# Chip_Inputs.net
KiCad netlist of a schematic drawn in Altium Designer
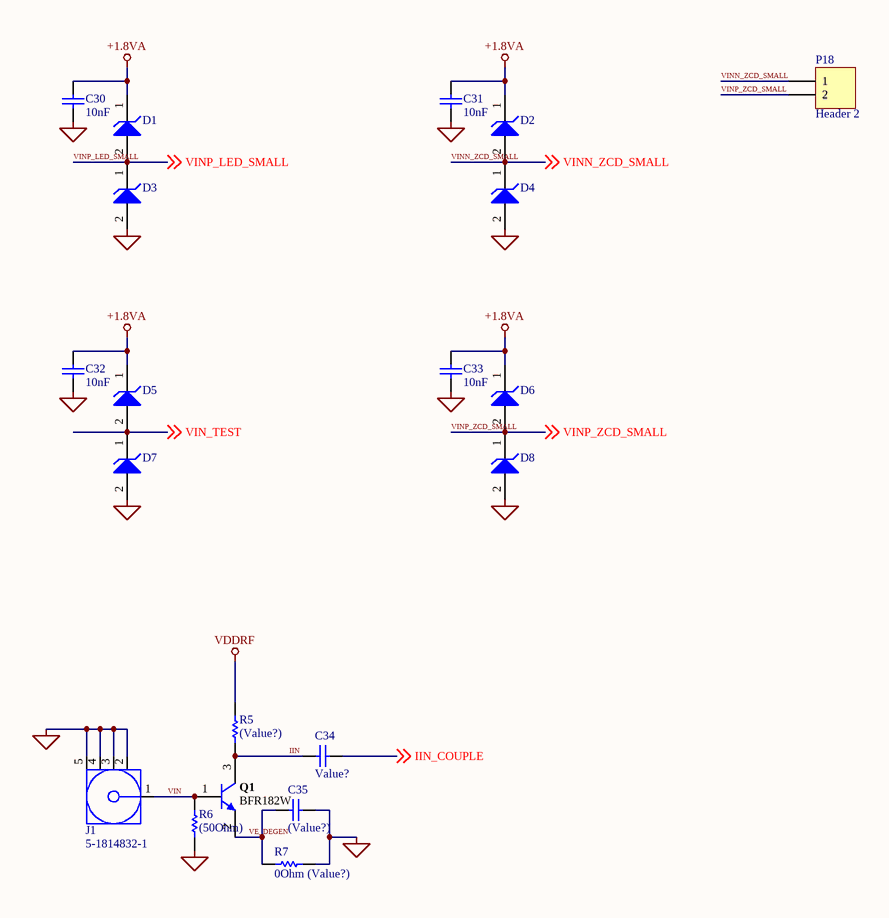
[diagram p0: Chip_Inputs.SchDoc]

(export (version "E")
  (design (tool "Eeschema 10.0.6"))
  (components
    (comp (ref "C30")
      (value "10nF")
      (footprint "CAPC1608X90X35ML10T15")
      (description "0603")
      (fields (field (name "MANUFACTURER") "Murata"))
      (libsource (lib "Altium Content Vault") (part "CAP-NP-2"))
    )
    (comp (ref "C31")
      (value "10nF")
      (footprint "CAPC1608X90X35ML10T15")
      (description "0603")
      (fields (field (name "MANUFACTURER") "Murata"))
      (libsource (lib "Altium Content Vault") (part "CAP-NP-2"))
    )
    (comp (ref "C32")
      (value "10nF")
      (footprint "CAPC1608X90X35ML10T15")
      (description "0603")
      (fields (field (name "MANUFACTURER") "Murata"))
      (libsource (lib "Altium Content Vault") (part "CAP-NP-2"))
    )
    (comp (ref "C33")
      (value "10nF")
      (footprint "CAPC1608X90X35ML10T15")
      (description "0603")
      (fields (field (name "MANUFACTURER") "Murata"))
      (libsource (lib "Altium Content Vault") (part "CAP-NP-2"))
    )
    (comp (ref "C34")
      (value "Value?")
      (footprint "CAPC1608X90X35ML10T15")
      (description "0603")
      (fields (field (name "MANUFACTURER") "Murata"))
      (libsource (lib "Altium Content Vault") (part "CAP-NP-2"))
    )
    (comp (ref "C35")
      (value "(Value?)")
      (footprint "CAPC1608X90X35ML10T15")
      (description "0603")
      (fields (field (name "MANUFACTURER") "Murata"))
      (libsource (lib "Altium Content Vault") (part "CAP-NP-2"))
    )
    (comp (ref "D1")
      (value "~")
      (footprint "ONSC-SOD-123-2-425-04_V")
      (description "Zener Voltage Regulator, 2-Pin SOD-123, Pb-Free, Tape and Reel")
      (fields (field (name "MANUFACTURER") "On Semiconductor") (field (name "PARTNUMBER") "MMSZ4679T1G"))
      (libsource (lib "Altium Content Vault") (part "ONSC-K1A2-2"))
    )
    (comp (ref "D2")
      (value "~")
      (footprint "ONSC-SOD-123-2-425-04_V")
      (description "Zener Voltage Regulator, 2-Pin SOD-123, Pb-Free, Tape and Reel")
      (fields (field (name "MANUFACTURER") "On Semiconductor") (field (name "PARTNUMBER") "MMSZ4679T1G"))
      (libsource (lib "Altium Content Vault") (part "ONSC-K1A2-2"))
    )
    (comp (ref "D3")
      (value "~")
      (footprint "ONSC-SOD-123-2-425-04_V")
      (description "Zener Voltage Regulator, 2-Pin SOD-123, Pb-Free, Tape and Reel")
      (fields (field (name "MANUFACTURER") "On Semiconductor") (field (name "PARTNUMBER") "MMSZ4679T1G"))
      (libsource (lib "Altium Content Vault") (part "ONSC-K1A2-2"))
    )
    (comp (ref "D4")
      (value "~")
      (footprint "ONSC-SOD-123-2-425-04_V")
      (description "Zener Voltage Regulator, 2-Pin SOD-123, Pb-Free, Tape and Reel")
      (fields (field (name "MANUFACTURER") "On Semiconductor") (field (name "PARTNUMBER") "MMSZ4679T1G"))
      (libsource (lib "Altium Content Vault") (part "ONSC-K1A2-2"))
    )
    (comp (ref "D5")
      (value "~")
      (footprint "ONSC-SOD-123-2-425-04_V")
      (description "Zener Voltage Regulator, 2-Pin SOD-123, Pb-Free, Tape and Reel")
      (fields (field (name "MANUFACTURER") "On Semiconductor") (field (name "PARTNUMBER") "MMSZ4679T1G"))
      (libsource (lib "Altium Content Vault") (part "ONSC-K1A2-2"))
    )
    (comp (ref "D6")
      (value "~")
      (footprint "ONSC-SOD-123-2-425-04_V")
      (description "Zener Voltage Regulator, 2-Pin SOD-123, Pb-Free, Tape and Reel")
      (fields (field (name "MANUFACTURER") "On Semiconductor") (field (name "PARTNUMBER") "MMSZ4679T1G"))
      (libsource (lib "Altium Content Vault") (part "ONSC-K1A2-2"))
    )
    (comp (ref "D7")
      (value "~")
      (footprint "ONSC-SOD-123-2-425-04_V")
      (description "Zener Voltage Regulator, 2-Pin SOD-123, Pb-Free, Tape and Reel")
      (fields (field (name "MANUFACTURER") "On Semiconductor") (field (name "PARTNUMBER") "MMSZ4679T1G"))
      (libsource (lib "Altium Content Vault") (part "ONSC-K1A2-2"))
    )
    (comp (ref "D8")
      (value "~")
      (footprint "ONSC-SOD-123-2-425-04_V")
      (description "Zener Voltage Regulator, 2-Pin SOD-123, Pb-Free, Tape and Reel")
      (fields (field (name "MANUFACTURER") "On Semiconductor") (field (name "PARTNUMBER") "MMSZ4679T1G"))
      (libsource (lib "Altium Content Vault") (part "ONSC-K1A2-2"))
    )
    (comp (ref "J1")
      (value "5-1814832-1")
      (footprint "TECO-5-1814832-1_V")
      (fields (field (name "MANUFACTURER") "TE Connectivity"))
      (libsource (lib "Altium Content Vault") (part "CN-S-4F-RF5"))
    )
    (comp (ref "P18")
      (value "Header 2")
      (footprint "HDR1X2")
      (description "Header, 2-Pin")
      (fields (field (name "PUBLISHER") "Altium Limited"))
      (libsource (lib "Miscellaneous Connectors") (part "Header 2"))
    )
    (comp (ref "Q1")
      (value "BFR182W")
      (footprint "INF-SOT323_L")
      (description "NPN Silicon RF Transistor, 12 V VCEO, 35 mA IC, 19 dB Gmax, SOT323, Green")
      (fields (field (name "MANUFACTURER") "Infineon"))
      (libsource (lib "Altium Content Vault") (part "INF-BFR182W-3"))
    )
    (comp (ref "R5")
      (value "(Value?)")
      (footprint "RESC1609X50X30NL8T20")
      (description "Chip Resistor, 0 Ohm, Jumper, 100 mW, -55 to 155 degC, 0603 (1608 Metric), RoHS, Tape and Reel")
      (fields (field (name "MANUFACTURER") "Vishay Semiconductor"))
      (libsource (lib "Altium Content Vault") (part "RES-2"))
    )
    (comp (ref "R6")
      (value "(50Ohm)")
      (footprint "RESC1609X50X30NL8T20")
      (description "Chip Resistor, 0 Ohm, Jumper, 100 mW, -55 to 155 degC, 0603 (1608 Metric), RoHS, Tape and Reel")
      (fields (field (name "MANUFACTURER") "Vishay Semiconductor"))
      (libsource (lib "Altium Content Vault") (part "RES-2"))
    )
    (comp (ref "R7")
      (value "0Ohm (Value?)")
      (footprint "RESC1609X50X30NL8T20")
      (description "Chip Resistor, 0 Ohm, Jumper, 100 mW, -55 to 155 degC, 0603 (1608 Metric), RoHS, Tape and Reel")
      (fields (field (name "MANUFACTURER") "Vishay Semiconductor"))
      (libsource (lib "Altium Content Vault") (part "RES-2"))
    )
  )
  (nets
    (net (code "1") (name "+1.8VA") (class "Default")
      (node (ref "C30") (pin "2") (pinfunction "2_2") (pintype "passive"))
      (node (ref "C31") (pin "2") (pinfunction "2_2") (pintype "passive"))
      (node (ref "C32") (pin "2") (pinfunction "2_2") (pintype "passive"))
      (node (ref "C33") (pin "2") (pinfunction "2_2") (pintype "passive"))
      (node (ref "D1") (pin "1") (pinfunction "K_1") (pintype "passive"))
      (node (ref "D2") (pin "1") (pinfunction "K_1") (pintype "passive"))
      (node (ref "D5") (pin "1") (pinfunction "K_1") (pintype "passive"))
      (node (ref "D6") (pin "1") (pinfunction "K_1") (pintype "passive"))
    )
    (net (code "2") (name "/IIN") (class "Default")
      (node (ref "C34") (pin "2") (pinfunction "2_2") (pintype "passive"))
      (node (ref "Q1") (pin "3") (pinfunction "C_3") (pintype "passive"))
      (node (ref "R5") (pin "1") (pinfunction "1_1") (pintype "passive"))
    )
    (net (code "3") (name "/VE_DEGEN") (class "Default")
      (node (ref "C35") (pin "2") (pinfunction "2_2") (pintype "passive"))
      (node (ref "Q1") (pin "2") (pinfunction "E_2") (pintype "passive"))
      (node (ref "R7") (pin "2") (pinfunction "2_2") (pintype "passive"))
    )
    (net (code "4") (name "/VIN") (class "Default")
      (node (ref "J1") (pin "1") (pinfunction "1_1") (pintype "passive"))
      (node (ref "Q1") (pin "1") (pinfunction "B_1") (pintype "passive"))
      (node (ref "R6") (pin "2") (pinfunction "2_2") (pintype "passive"))
    )
    (net (code "5") (name "GND") (class "Default")
      (node (ref "C30") (pin "1") (pinfunction "1_1") (pintype "passive"))
      (node (ref "C31") (pin "1") (pinfunction "1_1") (pintype "passive"))
      (node (ref "C32") (pin "1") (pinfunction "1_1") (pintype "passive"))
      (node (ref "C33") (pin "1") (pinfunction "1_1") (pintype "passive"))
      (node (ref "C35") (pin "1") (pinfunction "1_1") (pintype "passive"))
      (node (ref "D3") (pin "2") (pinfunction "A_2") (pintype "passive"))
      (node (ref "D4") (pin "2") (pinfunction "A_2") (pintype "passive"))
      (node (ref "D7") (pin "2") (pinfunction "A_2") (pintype "passive"))
      (node (ref "D8") (pin "2") (pinfunction "A_2") (pintype "passive"))
      (node (ref "J1") (pin "2") (pinfunction "2_2") (pintype "passive"))
      (node (ref "J1") (pin "3") (pinfunction "3_3") (pintype "passive"))
      (node (ref "J1") (pin "4") (pinfunction "4_4") (pintype "passive"))
      (node (ref "J1") (pin "5") (pinfunction "5_5") (pintype "passive"))
      (node (ref "R6") (pin "1") (pinfunction "1_1") (pintype "passive"))
      (node (ref "R7") (pin "1") (pinfunction "1_1") (pintype "passive"))
    )
    (net (code "6") (name "IIN_COUPLE") (class "Default")
      (node (ref "C34") (pin "1") (pinfunction "1_1") (pintype "passive"))
    )
    (net (code "7") (name "VDDRF") (class "Default")
      (node (ref "R5") (pin "2") (pinfunction "2_2") (pintype "passive"))
    )
    (net (code "8") (name "VINN_ZCD_SMALL") (class "Default")
      (node (ref "D2") (pin "2") (pinfunction "A_2") (pintype "passive"))
      (node (ref "D4") (pin "1") (pinfunction "K_1") (pintype "passive"))
      (node (ref "P18") (pin "1") (pinfunction "1_1") (pintype "passive"))
    )
    (net (code "9") (name "VINP_LED_SMALL") (class "Default")
      (node (ref "D1") (pin "2") (pinfunction "A_2") (pintype "passive"))
      (node (ref "D3") (pin "1") (pinfunction "K_1") (pintype "passive"))
    )
    (net (code "10") (name "VINP_ZCD_SMALL") (class "Default")
      (node (ref "D6") (pin "2") (pinfunction "A_2") (pintype "passive"))
      (node (ref "D8") (pin "1") (pinfunction "K_1") (pintype "passive"))
      (node (ref "P18") (pin "2") (pinfunction "2_2") (pintype "passive"))
    )
    (net (code "11") (name "VIN_TEST") (class "Default")
      (node (ref "D5") (pin "2") (pinfunction "A_2") (pintype "passive"))
      (node (ref "D7") (pin "1") (pinfunction "K_1") (pintype "passive"))
    )
  )
)
